# lcd_ultrassonico.net
KiCad netlist of a schematic drawn in EAGLE
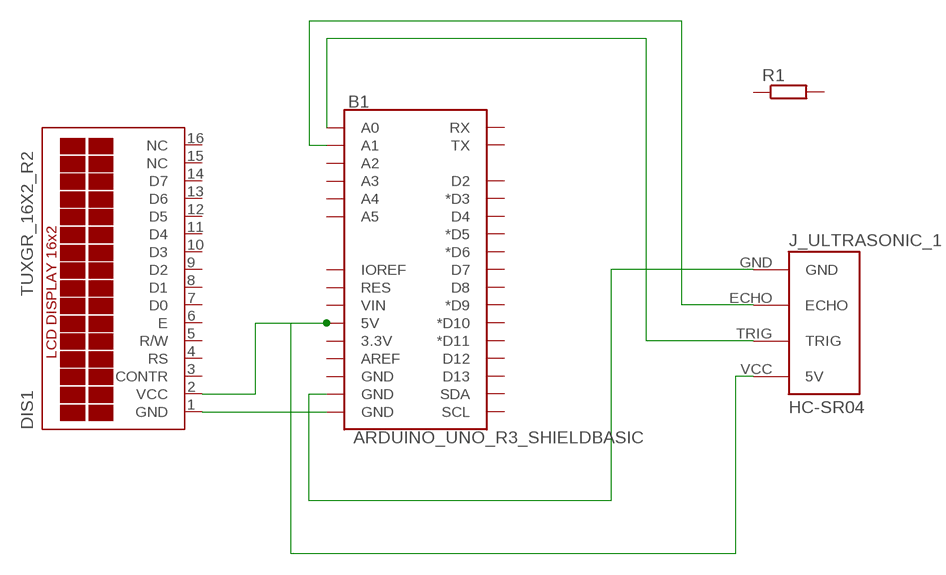
[diagram p0: schematic, sheet 1]

(export (version "E")
  (design (tool "Eeschema 10.0.6"))
  (components
    (comp (ref "B1")
      (value "ARDUINO_UNO_R3_SHIELDBASIC")
      (footprint "eagle-import:UNO_R3_SHIELD")
      (libsource (lib "eagle-import") (part "ARDUINO_UNO_R3_SHIELDBASIC"))
    )
    (comp (ref "DIS1")
      (value "TUXGR_16X2_R2")
      (footprint "eagle-import:TUXGR_16X2_R2")
      (libsource (lib "eagle-import") (part "TUXGR_16X2_R2"))
    )
    (comp (ref "J_ULTRASONIC_1")
      (value "HC-SR04")
      (footprint "eagle-import:HC-SR04_FOOTPRINT")
      (libsource (lib "eagle-import") (part "HC-SR04"))
    )
    (comp (ref "R1")
      (value "R-EU_0204/7")
      (footprint "eagle-import:0204_7")
      (libsource (lib "eagle-import") (part "R-EU_0204/7"))
    )
  )
  (nets
    (net (code "1") (name "Net-(B1-GND-PadGND@1)") (class "Default")
      (node (ref "B1") (pin "GND@1") (pinfunction "GND_GND@1") (pintype "bidirectional"))
      (node (ref "J_ULTRASONIC_1") (pin "GND") (pinfunction "GND_GND") (pintype "bidirectional"))
    )
    (net (code "2") (name "Net-(B1-PadA0)") (class "Default")
      (node (ref "B1") (pin "A0") (pinfunction "A0_A0") (pintype "bidirectional"))
      (node (ref "J_ULTRASONIC_1") (pin "TRIG") (pinfunction "TRIG_TRIG") (pintype "bidirectional"))
    )
    (net (code "3") (name "Net-(B1-PadA1)") (class "Default")
      (node (ref "B1") (pin "A1") (pinfunction "A1_A1") (pintype "bidirectional"))
      (node (ref "J_ULTRASONIC_1") (pin "ECHO") (pinfunction "ECHO_ECHO") (pintype "bidirectional"))
    )
    (net (code "4") (name "Net-(DIS1-GND)") (class "Default")
      (node (ref "B1") (pin "GND@0") (pinfunction "GND_GND@0") (pintype "bidirectional"))
      (node (ref "DIS1") (pin "1") (pinfunction "GND_1") (pintype "power_in"))
    )
    (net (code "5") (name "Net-(DIS1-VCC)") (class "Default")
      (node (ref "B1") (pin "5V") (pinfunction "5V_5V") (pintype "bidirectional"))
      (node (ref "DIS1") (pin "2") (pinfunction "VCC_2") (pintype "power_in"))
      (node (ref "J_ULTRASONIC_1") (pin "VCC") (pinfunction "5V_VCC") (pintype "bidirectional"))
    )
    (net (code "6") (name "unconnected-(B1-*D3-PadD3)") (class "Default")
      (node (ref "B1") (pin "D3") (pinfunction "*D3_D3") (pintype "bidirectional"))
    )
    (net (code "7") (name "unconnected-(B1-*D5-PadD5)") (class "Default")
      (node (ref "B1") (pin "D5") (pinfunction "*D5_D5") (pintype "bidirectional"))
    )
    (net (code "8") (name "unconnected-(B1-*D6-PadD6)") (class "Default")
      (node (ref "B1") (pin "D6") (pinfunction "*D6_D6") (pintype "bidirectional"))
    )
    (net (code "9") (name "unconnected-(B1-*D9-PadD9)") (class "Default")
      (node (ref "B1") (pin "D9") (pinfunction "*D9_D9") (pintype "bidirectional"))
    )
    (net (code "10") (name "unconnected-(B1-*D10-PadD10)") (class "Default")
      (node (ref "B1") (pin "D10") (pinfunction "*D10_D10") (pintype "bidirectional"))
    )
    (net (code "11") (name "unconnected-(B1-*D11-PadD11)") (class "Default")
      (node (ref "B1") (pin "D11") (pinfunction "*D11_D11") (pintype "bidirectional"))
    )
    (net (code "12") (name "unconnected-(B1-GND-PadGND@2)") (class "Default")
      (node (ref "B1") (pin "GND@2") (pinfunction "GND_GND@2") (pintype "bidirectional"))
    )
    (net (code "13") (name "unconnected-(B1-Pad3.3V)") (class "Default")
      (node (ref "B1") (pin "3.3V") (pinfunction "3.3V_3.3V") (pintype "bidirectional"))
    )
    (net (code "14") (name "unconnected-(B1-PadA2)") (class "Default")
      (node (ref "B1") (pin "A2") (pinfunction "A2_A2") (pintype "bidirectional"))
    )
    (net (code "15") (name "unconnected-(B1-PadA3)") (class "Default")
      (node (ref "B1") (pin "A3") (pinfunction "A3_A3") (pintype "bidirectional"))
    )
    (net (code "16") (name "unconnected-(B1-PadA4)") (class "Default")
      (node (ref "B1") (pin "A4") (pinfunction "A4_A4") (pintype "bidirectional"))
    )
    (net (code "17") (name "unconnected-(B1-PadA5)") (class "Default")
      (node (ref "B1") (pin "A5") (pinfunction "A5_A5") (pintype "bidirectional"))
    )
    (net (code "18") (name "unconnected-(B1-PadAREF)") (class "Default")
      (node (ref "B1") (pin "AREF") (pinfunction "AREF_AREF") (pintype "bidirectional"))
    )
    (net (code "19") (name "unconnected-(B1-PadD2)") (class "Default")
      (node (ref "B1") (pin "D2") (pinfunction "D2_D2") (pintype "bidirectional"))
    )
    (net (code "20") (name "unconnected-(B1-PadD4)") (class "Default")
      (node (ref "B1") (pin "D4") (pinfunction "D4_D4") (pintype "bidirectional"))
    )
    (net (code "21") (name "unconnected-(B1-PadD7)") (class "Default")
      (node (ref "B1") (pin "D7") (pinfunction "D7_D7") (pintype "bidirectional"))
    )
    (net (code "22") (name "unconnected-(B1-PadD8)") (class "Default")
      (node (ref "B1") (pin "D8") (pinfunction "D8_D8") (pintype "bidirectional"))
    )
    (net (code "23") (name "unconnected-(B1-PadD12)") (class "Default")
      (node (ref "B1") (pin "D12") (pinfunction "D12_D12") (pintype "bidirectional"))
    )
    (net (code "24") (name "unconnected-(B1-PadD13)") (class "Default")
      (node (ref "B1") (pin "D13") (pinfunction "D13_D13") (pintype "bidirectional"))
    )
    (net (code "25") (name "unconnected-(B1-PadIOREF)") (class "Default")
      (node (ref "B1") (pin "IOREF") (pinfunction "IOREF_IOREF") (pintype "bidirectional"))
    )
    (net (code "26") (name "unconnected-(B1-PadRES)") (class "Default")
      (node (ref "B1") (pin "RES") (pinfunction "RES_RES") (pintype "bidirectional"))
    )
    (net (code "27") (name "unconnected-(B1-PadRX)") (class "Default")
      (node (ref "B1") (pin "RX") (pinfunction "RX_RX") (pintype "bidirectional"))
    )
    (net (code "28") (name "unconnected-(B1-PadSCL)") (class "Default")
      (node (ref "B1") (pin "SCL") (pinfunction "SCL_SCL") (pintype "bidirectional"))
    )
    (net (code "29") (name "unconnected-(B1-PadSDA)") (class "Default")
      (node (ref "B1") (pin "SDA") (pinfunction "SDA_SDA") (pintype "bidirectional"))
    )
    (net (code "30") (name "unconnected-(B1-PadTX)") (class "Default")
      (node (ref "B1") (pin "TX") (pinfunction "TX_TX") (pintype "bidirectional"))
    )
    (net (code "31") (name "unconnected-(B1-PadVIN)") (class "Default")
      (node (ref "B1") (pin "VIN") (pinfunction "VIN_VIN") (pintype "bidirectional"))
    )
    (net (code "32") (name "unconnected-(DIS1-CONTR-Pad3)") (class "Default")
      (node (ref "DIS1") (pin "3") (pinfunction "CONTR_3") (pintype "input"))
    )
    (net (code "33") (name "unconnected-(DIS1-D0-Pad7)") (class "Default")
      (node (ref "DIS1") (pin "7") (pinfunction "D0_7") (pintype "input"))
    )
    (net (code "34") (name "unconnected-(DIS1-D1-Pad8)") (class "Default")
      (node (ref "DIS1") (pin "8") (pinfunction "D1_8") (pintype "input"))
    )
    (net (code "35") (name "unconnected-(DIS1-D2-Pad9)") (class "Default")
      (node (ref "DIS1") (pin "9") (pinfunction "D2_9") (pintype "input"))
    )
    (net (code "36") (name "unconnected-(DIS1-D3-Pad10)") (class "Default")
      (node (ref "DIS1") (pin "10") (pinfunction "D3_10") (pintype "input"))
    )
    (net (code "37") (name "unconnected-(DIS1-D4-Pad11)") (class "Default")
      (node (ref "DIS1") (pin "11") (pinfunction "D4_11") (pintype "input"))
    )
    (net (code "38") (name "unconnected-(DIS1-D5-Pad12)") (class "Default")
      (node (ref "DIS1") (pin "12") (pinfunction "D5_12") (pintype "input"))
    )
    (net (code "39") (name "unconnected-(DIS1-D6-Pad13)") (class "Default")
      (node (ref "DIS1") (pin "13") (pinfunction "D6_13") (pintype "input"))
    )
    (net (code "40") (name "unconnected-(DIS1-D7-Pad14)") (class "Default")
      (node (ref "DIS1") (pin "14") (pinfunction "D7_14") (pintype "input"))
    )
    (net (code "41") (name "unconnected-(DIS1-E-Pad6)") (class "Default")
      (node (ref "DIS1") (pin "6") (pinfunction "E_6") (pintype "input"))
    )
    (net (code "42") (name "unconnected-(DIS1-NC-Pad15)") (class "Default")
      (node (ref "DIS1") (pin "15") (pinfunction "NC_15") (pintype "no_connect"))
    )
    (net (code "43") (name "unconnected-(DIS1-NC-Pad16)") (class "Default")
      (node (ref "DIS1") (pin "16") (pinfunction "NC_16") (pintype "no_connect"))
    )
    (net (code "44") (name "unconnected-(DIS1-RS-Pad4)") (class "Default")
      (node (ref "DIS1") (pin "4") (pinfunction "RS_4") (pintype "input"))
    )
    (net (code "45") (name "unconnected-(DIS1-R{slash}W-Pad5)") (class "Default")
      (node (ref "DIS1") (pin "5") (pinfunction "R/W_5") (pintype "input"))
    )
    (net (code "46") (name "unconnected-(R1-Pad1)") (class "Default")
      (node (ref "R1") (pin "1") (pinfunction "1_1") (pintype "passive"))
    )
    (net (code "47") (name "unconnected-(R1-Pad2)") (class "Default")
      (node (ref "R1") (pin "2") (pinfunction "2_2") (pintype "passive"))
    )
  )
)
